# conn_board_interfaces.net
KiCad netlist of a schematic drawn in Altium Designer
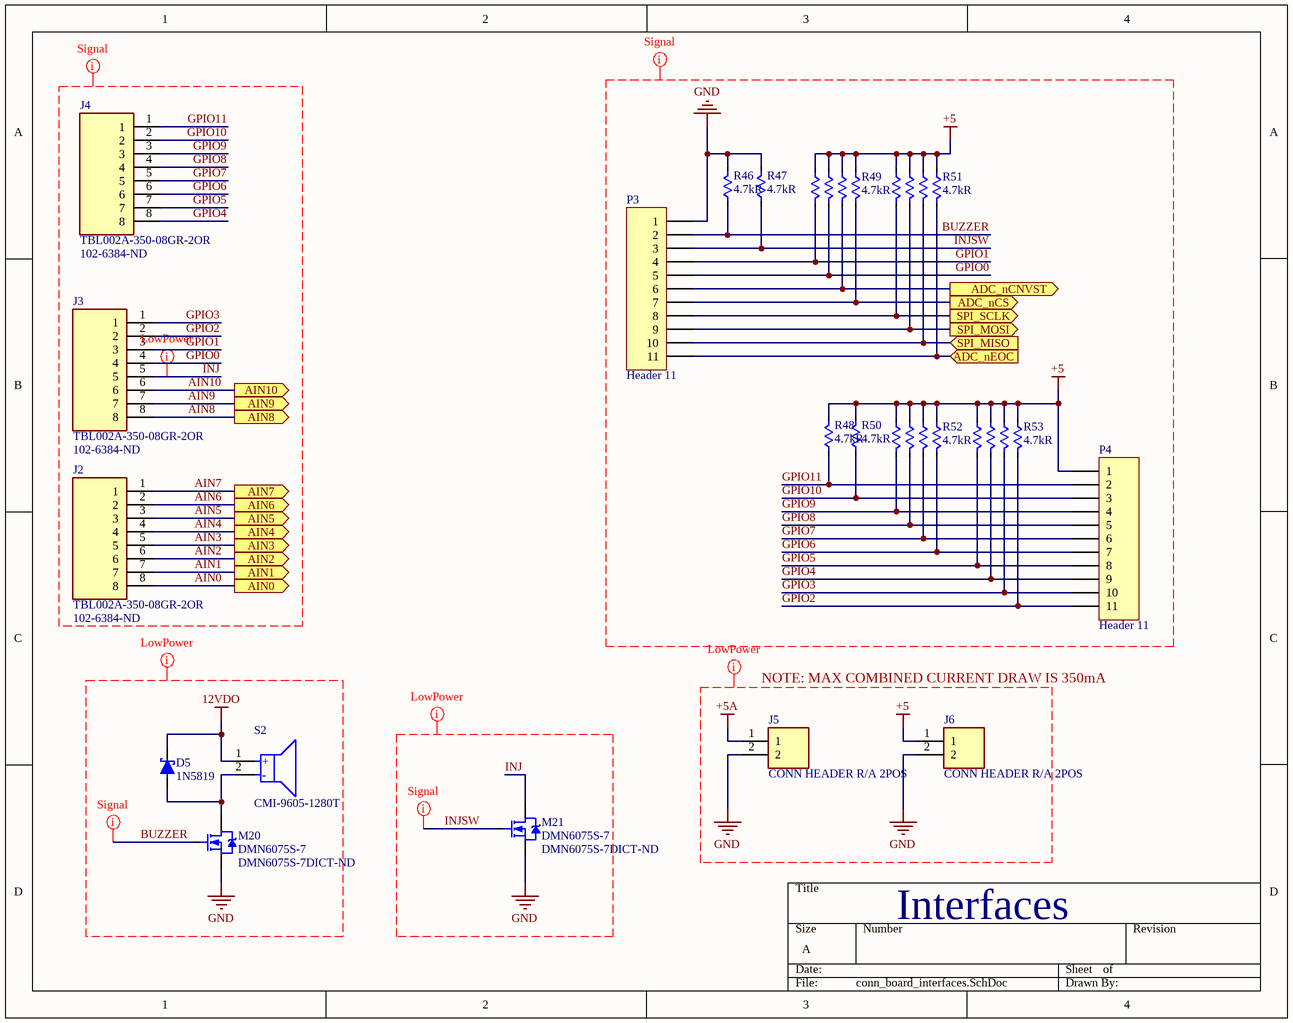
[diagram p0: conn_board_interfaces.SchDoc]

(export (version "E")
  (design (tool "Eeschema 10.0.6"))
  (components
    (comp (ref "D5")
      (value "1N5819")
      (footprint "SOD123")
      (description "DIODES INC. - 1N5819HW-7-F - DIODE, SCKY RECTI, 1A, 40V, SOD123")
      (fields (field (name "MANUFACTURER") "Diodes") (field (name "MANUFACTURER PART NUMBER") "1N5819HW-7-F"))
      (libsource (lib "Schlib1") (part "1N5819HW-7-F"))
    )
    (comp (ref "J2")
      (value "TBL002A-350-08GR-2OR")
      (footprint "CUI_TBL002A-350-08GR-2OR")
      (description "1~24 Poles, Screwless, 45Â°, 3.50 Pitch, 24~20 (AWG), Terminal Block Connector")
      (fields (field (name "MF") "CUI Devices") (field (name "SUPPLIER PART NUMBER 1") "102-6384-ND"))
      (libsource (lib "Schlib1") (part "TBL002A-350-08GR-2OR"))
    )
    (comp (ref "J3")
      (value "TBL002A-350-08GR-2OR")
      (footprint "CUI_TBL002A-350-08GR-2OR")
      (description "1~24 Poles, Screwless, 45Â°, 3.50 Pitch, 24~20 (AWG), Terminal Block Connector")
      (fields (field (name "MF") "CUI Devices") (field (name "SUPPLIER PART NUMBER 1") "102-6384-ND"))
      (libsource (lib "Schlib1") (part "TBL002A-350-08GR-2OR"))
    )
    (comp (ref "J4")
      (value "TBL002A-350-08GR-2OR")
      (footprint "CUI_TBL002A-350-08GR-2OR")
      (description "1~24 Poles, Screwless, 45Â°, 3.50 Pitch, 24~20 (AWG), Terminal Block Connector")
      (fields (field (name "MF") "CUI Devices") (field (name "SUPPLIER PART NUMBER 1") "102-6384-ND"))
      (libsource (lib "Schlib1") (part "TBL002A-350-08GR-2OR"))
    )
    (comp (ref "J5")
      (value "CONN HEADER R/A 2POS")
      (footprint "2 POS MOLEX")
      (fields (field (name "MANUFACTURER") "Molex") (field (name "MANUFACTURER PART NUMBER") "1724480002"))
      (libsource (lib "Schlib1") (part "1724480002"))
    )
    (comp (ref "J6")
      (value "CONN HEADER R/A 2POS")
      (footprint "2 POS MOLEX")
      (fields (field (name "MANUFACTURER") "Molex") (field (name "MANUFACTURER PART NUMBER") "1724480002"))
      (libsource (lib "Schlib1") (part "1724480002"))
    )
    (comp (ref "M20")
      (value "DMN6075S-7")
      (footprint "FP-SOT23-MFG")
      (description "MOSFET 60V N-Ch Enh FET 20Vgss 0.8W 600pF")
      (fields
        (field (name "MANUFACTURER") "Diodes Inc.")
        (field (name "OCTOPART") "https://octopart.com/dmn6075s-7-diodes+inc.-55697882")
        (field (name "SUPPLIER PART NUMBER 1") "DMN6075S-7DICT-ND")
      )
      (libsource (lib "Schlib1") (part "CMP-12801-000014-1"))
    )
    (comp (ref "M21")
      (value "DMN6075S-7")
      (footprint "FP-SOT23-MFG")
      (description "MOSFET 60V N-Ch Enh FET 20Vgss 0.8W 600pF")
      (fields
        (field (name "MANUFACTURER") "Diodes Inc.")
        (field (name "OCTOPART") "https://octopart.com/dmn6075s-7-diodes+inc.-55697882")
        (field (name "SUPPLIER PART NUMBER 1") "DMN6075S-7DICT-ND")
      )
      (libsource (lib "Schlib1") (part "CMP-12801-000014-1"))
    )
    (comp (ref "P3")
      (value "Header 11")
      (footprint "HDR1X11")
      (description "Header, 11-Pin")
      (fields (field (name "PUBLISHER") "Altium Limited"))
      (libsource (lib "") (part "Header 11_1"))
    )
    (comp (ref "P4")
      (value "Header 11")
      (footprint "HDR1X11")
      (description "Header, 11-Pin")
      (fields (field (name "PUBLISHER") "Altium Limited"))
      (libsource (lib "Miscellaneous Connectors") (part "Header 11"))
    )
    (comp (ref "R46")
      (value "4.7kR")
      (footprint "RES_0805_PANASONIC")
      (description "Res Thin Film 0805 4.7K Ohm 0.5% 0.125W(1/8W) ±25ppm/C Molded SMD Automotive Punched T/R")
      (fields
        (field (name "MANUFACTURER") "Panasonic")
        (field (name "MANUFACTURER PART NUMBER") "ERA-6AED472V")
      )
      (libsource (lib "Schlib1") (part "ERA-6AED472V"))
    )
    (comp (ref "R47")
      (value "4.7kR")
      (footprint "RES_0805_PANASONIC")
      (description "Res Thin Film 0805 4.7K Ohm 0.5% 0.125W(1/8W) ±25ppm/C Molded SMD Automotive Punched T/R")
      (fields
        (field (name "MANUFACTURER") "Panasonic")
        (field (name "MANUFACTURER PART NUMBER") "ERA-6AED472V")
      )
      (libsource (lib "Schlib1") (part "ERA-6AED472V"))
    )
    (comp (ref "R48")
      (value "4.7kR")
      (footprint "RES_0805_PANASONIC")
      (description "Res Thin Film 0805 4.7K Ohm 0.5% 0.125W(1/8W) ±25ppm/C Molded SMD Automotive Punched T/R")
      (fields
        (field (name "MANUFACTURER") "Panasonic")
        (field (name "MANUFACTURER PART NUMBER") "ERA-6AED472V")
      )
      (libsource (lib "Schlib1") (part "ERA-6AED472V"))
    )
    (comp (ref "R49")
      (value "4.7kR")
      (footprint "CAY16-472J4LF")
      (description "RES ARRAY 4 RES 4.7K OHM 1206")
      (fields
        (field (name "MANUFACTURER") "Bourns")
        (field (name "MANUFACTURER PART NUMBER") "CAY16-472J4LF")
      )
      (libsource (lib "Schlib1") (part "CAY16-472J4LF"))
    )
    (comp (ref "R50")
      (value "4.7kR")
      (footprint "RES_0805_PANASONIC")
      (description "Res Thin Film 0805 4.7K Ohm 0.5% 0.125W(1/8W) ±25ppm/C Molded SMD Automotive Punched T/R")
      (fields
        (field (name "MANUFACTURER") "Panasonic")
        (field (name "MANUFACTURER PART NUMBER") "ERA-6AED472V")
      )
      (libsource (lib "Schlib1") (part "ERA-6AED472V"))
    )
    (comp (ref "R51")
      (value "4.7kR")
      (footprint "CAY16-472J4LF")
      (description "RES ARRAY 4 RES 4.7K OHM 1206")
      (fields
        (field (name "MANUFACTURER") "Bourns")
        (field (name "MANUFACTURER PART NUMBER") "CAY16-472J4LF")
      )
      (libsource (lib "Schlib1") (part "CAY16-472J4LF"))
    )
    (comp (ref "R52")
      (value "4.7kR")
      (footprint "CAY16-472J4LF")
      (description "RES ARRAY 4 RES 4.7K OHM 1206")
      (fields
        (field (name "MANUFACTURER") "Bourns")
        (field (name "MANUFACTURER PART NUMBER") "CAY16-472J4LF")
      )
      (libsource (lib "Schlib1") (part "CAY16-472J4LF"))
    )
    (comp (ref "R53")
      (value "4.7kR")
      (footprint "CAY16-472J4LF")
      (description "RES ARRAY 4 RES 4.7K OHM 1206")
      (fields
        (field (name "MANUFACTURER") "Bourns")
        (field (name "MANUFACTURER PART NUMBER") "CAY16-472J4LF")
      )
      (libsource (lib "Schlib1") (part "CAY16-472J4LF"))
    )
    (comp (ref "S2")
      (value "CMI-9605-1280T")
      (footprint "CMI-9605-1280T")
      (fields (field (name "MANUFACTURER") "CUI"))
      (libsource (lib "Schlib1") (part "CMI-9605-1280T"))
    )
  )
  (nets
    (net (code "1") (name "+5") (class "Default")
      (node (ref "J6") (pin "1") (pinfunction "1_1") (pintype "passive"))
      (node (ref "P4") (pin "1") (pinfunction "1_1") (pintype "passive"))
      (node (ref "R48") (pin "2") (pinfunction "2_2") (pintype "passive"))
      (node (ref "R49") (pin "2") (pinfunction "2_2") (pintype "passive"))
      (node (ref "R49") (pin "4") (pinfunction "4_4") (pintype "passive"))
      (node (ref "R49") (pin "6") (pinfunction "6_6") (pintype "passive"))
      (node (ref "R49") (pin "8") (pinfunction "8_8") (pintype "passive"))
      (node (ref "R50") (pin "2") (pinfunction "2_2") (pintype "passive"))
      (node (ref "R51") (pin "2") (pinfunction "2_2") (pintype "passive"))
      (node (ref "R51") (pin "4") (pinfunction "4_4") (pintype "passive"))
      (node (ref "R51") (pin "6") (pinfunction "6_6") (pintype "passive"))
      (node (ref "R51") (pin "8") (pinfunction "8_8") (pintype "passive"))
      (node (ref "R52") (pin "2") (pinfunction "2_2") (pintype "passive"))
      (node (ref "R52") (pin "4") (pinfunction "4_4") (pintype "passive"))
      (node (ref "R52") (pin "6") (pinfunction "6_6") (pintype "passive"))
      (node (ref "R52") (pin "8") (pinfunction "8_8") (pintype "passive"))
      (node (ref "R53") (pin "2") (pinfunction "2_2") (pintype "passive"))
      (node (ref "R53") (pin "4") (pinfunction "4_4") (pintype "passive"))
      (node (ref "R53") (pin "6") (pinfunction "6_6") (pintype "passive"))
      (node (ref "R53") (pin "8") (pinfunction "8_8") (pintype "passive"))
    )
    (net (code "2") (name "+5A") (class "Default")
      (node (ref "J5") (pin "1") (pinfunction "1_1") (pintype "passive"))
    )
    (net (code "3") (name "/ADC_nCNVST") (class "Default")
      (node (ref "P3") (pin "6") (pinfunction "6_6") (pintype "passive"))
      (node (ref "R49") (pin "5") (pinfunction "5_5") (pintype "passive"))
    )
    (net (code "4") (name "/ADC_nCS") (class "Default")
      (node (ref "P3") (pin "7") (pinfunction "7_7") (pintype "passive"))
      (node (ref "R49") (pin "7") (pinfunction "7_7") (pintype "passive"))
    )
    (net (code "5") (name "/ADC_nEOC") (class "Default")
      (node (ref "P3") (pin "11") (pinfunction "11_11") (pintype "passive"))
      (node (ref "R51") (pin "7") (pinfunction "7_7") (pintype "passive"))
    )
    (net (code "6") (name "/AIN0") (class "Default")
      (node (ref "J2") (pin "8") (pinfunction "8_8") (pintype "passive"))
    )
    (net (code "7") (name "/AIN1") (class "Default")
      (node (ref "J2") (pin "7") (pinfunction "7_7") (pintype "passive"))
    )
    (net (code "8") (name "/AIN2") (class "Default")
      (node (ref "J2") (pin "6") (pinfunction "6_6") (pintype "passive"))
    )
    (net (code "9") (name "/AIN3") (class "Default")
      (node (ref "J2") (pin "5") (pinfunction "5_5") (pintype "passive"))
    )
    (net (code "10") (name "/AIN4") (class "Default")
      (node (ref "J2") (pin "4") (pinfunction "4_4") (pintype "passive"))
    )
    (net (code "11") (name "/AIN5") (class "Default")
      (node (ref "J2") (pin "3") (pinfunction "3_3") (pintype "passive"))
    )
    (net (code "12") (name "/AIN6") (class "Default")
      (node (ref "J2") (pin "2") (pinfunction "2_2") (pintype "passive"))
    )
    (net (code "13") (name "/AIN7") (class "Default")
      (node (ref "J2") (pin "1") (pinfunction "1_1") (pintype "passive"))
    )
    (net (code "14") (name "/AIN8") (class "Default")
      (node (ref "J3") (pin "8") (pinfunction "8_8") (pintype "passive"))
    )
    (net (code "15") (name "/AIN9") (class "Default")
      (node (ref "J3") (pin "7") (pinfunction "7_7") (pintype "passive"))
    )
    (net (code "16") (name "/AIN10") (class "Default")
      (node (ref "J3") (pin "6") (pinfunction "6_6") (pintype "passive"))
    )
    (net (code "17") (name "/BUZZER") (class "Default")
      (node (ref "M20") (pin "G") (pinfunction "G_G") (pintype "passive"))
      (node (ref "P3") (pin "2") (pinfunction "2_2") (pintype "passive"))
      (node (ref "R46") (pin "1") (pinfunction "1_1") (pintype "passive"))
    )
    (net (code "18") (name "/GPIO0") (class "Default")
      (node (ref "J3") (pin "4") (pinfunction "4_4") (pintype "passive"))
      (node (ref "P3") (pin "5") (pinfunction "5_5") (pintype "passive"))
      (node (ref "R49") (pin "3") (pinfunction "3_3") (pintype "passive"))
    )
    (net (code "19") (name "/GPIO1") (class "Default")
      (node (ref "J3") (pin "3") (pinfunction "3_3") (pintype "passive"))
      (node (ref "P3") (pin "4") (pinfunction "4_4") (pintype "passive"))
      (node (ref "R49") (pin "1") (pinfunction "1_1") (pintype "passive"))
    )
    (net (code "20") (name "/GPIO2") (class "Default")
      (node (ref "J3") (pin "2") (pinfunction "2_2") (pintype "passive"))
      (node (ref "P4") (pin "11") (pinfunction "11_11") (pintype "passive"))
      (node (ref "R53") (pin "7") (pinfunction "7_7") (pintype "passive"))
    )
    (net (code "21") (name "/GPIO3") (class "Default")
      (node (ref "J3") (pin "1") (pinfunction "1_1") (pintype "passive"))
      (node (ref "P4") (pin "10") (pinfunction "10_10") (pintype "passive"))
      (node (ref "R53") (pin "5") (pinfunction "5_5") (pintype "passive"))
    )
    (net (code "22") (name "/GPIO4") (class "Default")
      (node (ref "J4") (pin "8") (pinfunction "8_8") (pintype "passive"))
      (node (ref "P4") (pin "9") (pinfunction "9_9") (pintype "passive"))
      (node (ref "R53") (pin "3") (pinfunction "3_3") (pintype "passive"))
    )
    (net (code "23") (name "/GPIO5") (class "Default")
      (node (ref "J4") (pin "7") (pinfunction "7_7") (pintype "passive"))
      (node (ref "P4") (pin "8") (pinfunction "8_8") (pintype "passive"))
      (node (ref "R53") (pin "1") (pinfunction "1_1") (pintype "passive"))
    )
    (net (code "24") (name "/GPIO6") (class "Default")
      (node (ref "J4") (pin "6") (pinfunction "6_6") (pintype "passive"))
      (node (ref "P4") (pin "7") (pinfunction "7_7") (pintype "passive"))
      (node (ref "R52") (pin "7") (pinfunction "7_7") (pintype "passive"))
    )
    (net (code "25") (name "/GPIO7") (class "Default")
      (node (ref "J4") (pin "5") (pinfunction "5_5") (pintype "passive"))
      (node (ref "P4") (pin "6") (pinfunction "6_6") (pintype "passive"))
      (node (ref "R52") (pin "5") (pinfunction "5_5") (pintype "passive"))
    )
    (net (code "26") (name "/GPIO8") (class "Default")
      (node (ref "J4") (pin "4") (pinfunction "4_4") (pintype "passive"))
      (node (ref "P4") (pin "5") (pinfunction "5_5") (pintype "passive"))
      (node (ref "R52") (pin "3") (pinfunction "3_3") (pintype "passive"))
    )
    (net (code "27") (name "/GPIO9") (class "Default")
      (node (ref "J4") (pin "3") (pinfunction "3_3") (pintype "passive"))
      (node (ref "P4") (pin "4") (pinfunction "4_4") (pintype "passive"))
      (node (ref "R52") (pin "1") (pinfunction "1_1") (pintype "passive"))
    )
    (net (code "28") (name "/GPIO10") (class "Default")
      (node (ref "J4") (pin "2") (pinfunction "2_2") (pintype "passive"))
      (node (ref "P4") (pin "3") (pinfunction "3_3") (pintype "passive"))
      (node (ref "R50") (pin "1") (pinfunction "1_1") (pintype "passive"))
    )
    (net (code "29") (name "/GPIO11") (class "Default")
      (node (ref "J4") (pin "1") (pinfunction "1_1") (pintype "passive"))
      (node (ref "P4") (pin "2") (pinfunction "2_2") (pintype "passive"))
      (node (ref "R48") (pin "1") (pinfunction "1_1") (pintype "passive"))
    )
    (net (code "30") (name "/INJ") (class "Default")
      (node (ref "J3") (pin "5") (pinfunction "5_5") (pintype "passive"))
      (node (ref "M21") (pin "D") (pinfunction "D_D") (pintype "passive"))
    )
    (net (code "31") (name "/INJSW") (class "Default")
      (node (ref "M21") (pin "G") (pinfunction "G_G") (pintype "passive"))
      (node (ref "P3") (pin "3") (pinfunction "3_3") (pintype "passive"))
      (node (ref "R47") (pin "1") (pinfunction "1_1") (pintype "passive"))
    )
    (net (code "32") (name "/SPI_MISO") (class "Default")
      (node (ref "P3") (pin "10") (pinfunction "10_10") (pintype "passive"))
      (node (ref "R51") (pin "5") (pinfunction "5_5") (pintype "passive"))
    )
    (net (code "33") (name "/SPI_MOSI") (class "Default")
      (node (ref "P3") (pin "9") (pinfunction "9_9") (pintype "passive"))
      (node (ref "R51") (pin "3") (pinfunction "3_3") (pintype "passive"))
    )
    (net (code "34") (name "/SPI_SCLK") (class "Default")
      (node (ref "P3") (pin "8") (pinfunction "8_8") (pintype "passive"))
      (node (ref "R51") (pin "1") (pinfunction "1_1") (pintype "passive"))
    )
    (net (code "35") (name "12VDO") (class "Default")
      (node (ref "D5") (pin "1") (pinfunction "1_1") (pintype "passive"))
      (node (ref "S2") (pin "1") (pinfunction "+_1") (pintype "passive"))
    )
    (net (code "36") (name "GND") (class "Default")
      (node (ref "J5") (pin "2") (pinfunction "2_2") (pintype "passive"))
      (node (ref "J6") (pin "2") (pinfunction "2_2") (pintype "passive"))
      (node (ref "M20") (pin "S") (pinfunction "S_S") (pintype "passive"))
      (node (ref "M21") (pin "S") (pinfunction "S_S") (pintype "passive"))
      (node (ref "P3") (pin "1") (pinfunction "1_1") (pintype "passive"))
      (node (ref "R46") (pin "2") (pinfunction "2_2") (pintype "passive"))
      (node (ref "R47") (pin "2") (pinfunction "2_2") (pintype "passive"))
    )
    (net (code "37") (name "Net-(S2--)") (class "Default")
      (node (ref "D5") (pin "2") (pinfunction "2_2") (pintype "passive"))
      (node (ref "M20") (pin "D") (pinfunction "D_D") (pintype "passive"))
      (node (ref "S2") (pin "2") (pinfunction "-_2") (pintype "passive"))
    )
  )
)
